# COSEQ_shield.net
KiCad netlist of a schematic drawn in EAGLE
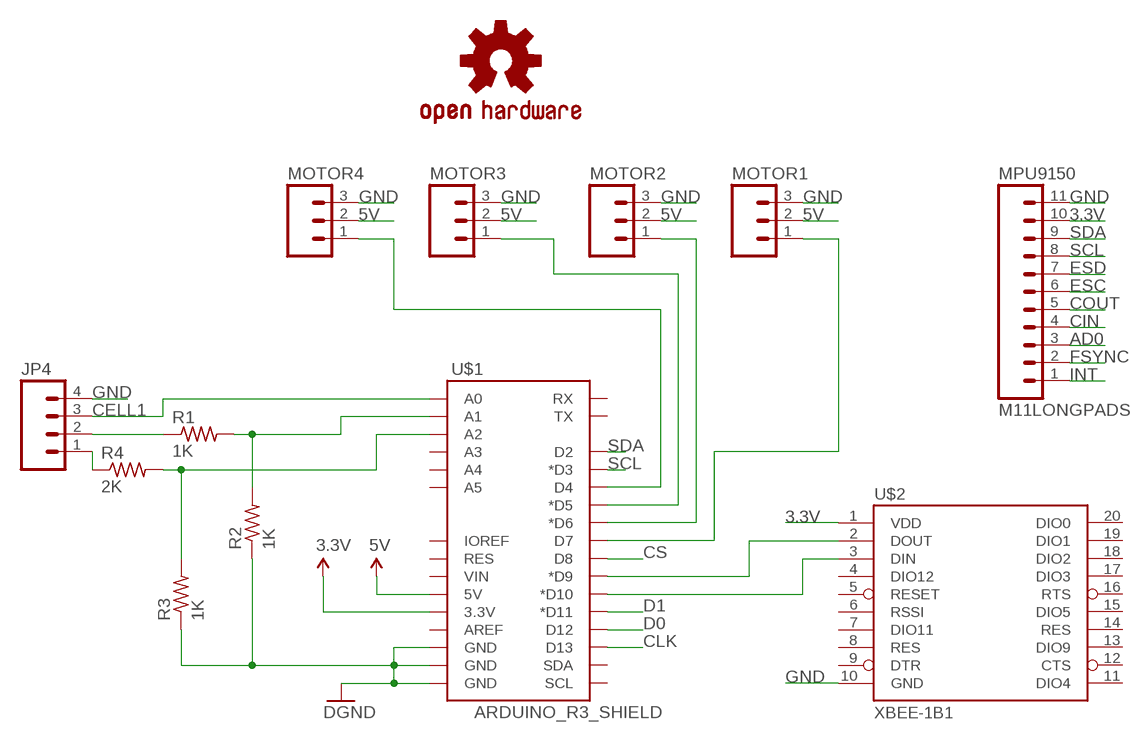
[diagram p0: schematic, sheet 1]

(export (version "E")
  (design (tool "Eeschema 10.0.6"))
  (components
    (comp (ref "JP4")
      (value "M04LONGPADS")
      (footprint "eagle-import:1X04_LONGPADS")
      (libsource (lib "eagle-import") (part "M04LONGPADS"))
    )
    (comp (ref "LOGO1")
      (value "OSHW-LOGOL")
      (footprint "eagle-import:OSHW-LOGO-L")
      (libsource (lib "eagle-import") (part "OSHW-LOGOL"))
    )
    (comp (ref "MOTOR1")
      (value "M03LONGPADS")
      (footprint "eagle-import:1X03_LONGPADS")
      (libsource (lib "eagle-import") (part "M03LONGPADS"))
    )
    (comp (ref "MOTOR2")
      (value "M03LONGPADS")
      (footprint "eagle-import:1X03_LONGPADS")
      (libsource (lib "eagle-import") (part "M03LONGPADS"))
    )
    (comp (ref "MOTOR3")
      (value "M03LONGPADS")
      (footprint "eagle-import:1X03_LONGPADS")
      (libsource (lib "eagle-import") (part "M03LONGPADS"))
    )
    (comp (ref "MOTOR4")
      (value "M03LONGPADS")
      (footprint "eagle-import:1X03_LONGPADS")
      (libsource (lib "eagle-import") (part "M03LONGPADS"))
    )
    (comp (ref "MPU9150")
      (value "M11LONGPADS")
      (footprint "eagle-import:1X11_LONGPADS")
      (libsource (lib "eagle-import") (part "M11LONGPADS"))
    )
    (comp (ref "R1")
      (value "1K")
      (footprint "eagle-import:RESISTOR")
      (libsource (lib "eagle-import") (part "RESISTOR1/6WATT"))
    )
    (comp (ref "R2")
      (value "1K")
      (footprint "eagle-import:RESISTOR")
      (libsource (lib "eagle-import") (part "RESISTOR1/6WATT"))
    )
    (comp (ref "R3")
      (value "1K")
      (footprint "eagle-import:RESISTOR")
      (libsource (lib "eagle-import") (part "RESISTOR1/6WATT"))
    )
    (comp (ref "R4")
      (value "2K")
      (footprint "eagle-import:RESISTOR")
      (libsource (lib "eagle-import") (part "RESISTOR1/6WATT"))
    )
    (comp (ref "U$1")
      (value "ARDUINO_R3_SHIELD")
      (footprint "eagle-import:UNO_R3_SHIELD")
      (libsource (lib "eagle-import") (part "ARDUINO_R3_SHIELD"))
    )
    (comp (ref "U$2")
      (value "XBEE-1B1")
      (footprint "eagle-import:XBEE-1")
      (libsource (lib "eagle-import") (part "XBEE-1B1"))
    )
  )
  (nets
    (net (code "1") (name "/AD0") (class "Default")
      (node (ref "MPU9150") (pin "3") (pinfunction "3_3") (pintype "passive"))
    )
    (net (code "2") (name "/CELL1") (class "Default")
      (node (ref "JP4") (pin "3") (pinfunction "3_3") (pintype "passive"))
      (node (ref "U$1") (pin "A0") (pinfunction "A0_A0") (pintype "bidirectional"))
    )
    (net (code "3") (name "/CIN") (class "Default")
      (node (ref "MPU9150") (pin "4") (pinfunction "4_4") (pintype "passive"))
    )
    (net (code "4") (name "/CLK") (class "Default")
      (node (ref "U$1") (pin "D13") (pinfunction "D13_D13") (pintype "bidirectional"))
    )
    (net (code "5") (name "/COUT") (class "Default")
      (node (ref "MPU9150") (pin "5") (pinfunction "5_5") (pintype "passive"))
    )
    (net (code "6") (name "/CS") (class "Default")
      (node (ref "U$1") (pin "D8") (pinfunction "D8_D8") (pintype "bidirectional"))
    )
    (net (code "7") (name "/D0") (class "Default")
      (node (ref "U$1") (pin "D12") (pinfunction "D12_D12") (pintype "bidirectional"))
    )
    (net (code "8") (name "/D1") (class "Default")
      (node (ref "U$1") (pin "D11") (pinfunction "*D11_D11") (pintype "bidirectional"))
    )
    (net (code "9") (name "/ESC") (class "Default")
      (node (ref "MPU9150") (pin "6") (pinfunction "6_6") (pintype "passive"))
    )
    (net (code "10") (name "/ESD") (class "Default")
      (node (ref "MPU9150") (pin "7") (pinfunction "7_7") (pintype "passive"))
    )
    (net (code "11") (name "/FSYNC") (class "Default")
      (node (ref "MPU9150") (pin "2") (pinfunction "2_2") (pintype "passive"))
    )
    (net (code "12") (name "/INT") (class "Default")
      (node (ref "MPU9150") (pin "1") (pinfunction "1_1") (pintype "passive"))
    )
    (net (code "13") (name "/SCL") (class "Default")
      (node (ref "MPU9150") (pin "8") (pinfunction "8_8") (pintype "passive"))
      (node (ref "U$1") (pin "D3") (pinfunction "*D3_D3") (pintype "bidirectional"))
    )
    (net (code "14") (name "/SDA") (class "Default")
      (node (ref "MPU9150") (pin "9") (pinfunction "9_9") (pintype "passive"))
      (node (ref "U$1") (pin "D2") (pinfunction "D2_D2") (pintype "bidirectional"))
    )
    (net (code "15") (name "3.3V") (class "Default")
      (node (ref "MPU9150") (pin "10") (pinfunction "10_10") (pintype "passive"))
      (node (ref "U$1") (pin "3.3V") (pinfunction "3.3V_3.3V") (pintype "bidirectional"))
      (node (ref "U$2") (pin "1") (pinfunction "VDD_1") (pintype "power_in"))
    )
    (net (code "16") (name "5V") (class "Default")
      (node (ref "MOTOR1") (pin "2") (pinfunction "2_2") (pintype "passive"))
      (node (ref "MOTOR2") (pin "2") (pinfunction "2_2") (pintype "passive"))
      (node (ref "MOTOR3") (pin "2") (pinfunction "2_2") (pintype "passive"))
      (node (ref "MOTOR4") (pin "2") (pinfunction "2_2") (pintype "passive"))
      (node (ref "U$1") (pin "5V") (pinfunction "5V_5V") (pintype "bidirectional"))
    )
    (net (code "17") (name "DGND") (class "Default")
      (node (ref "JP4") (pin "4") (pinfunction "4_4") (pintype "passive"))
      (node (ref "MOTOR1") (pin "3") (pinfunction "3_3") (pintype "passive"))
      (node (ref "MOTOR2") (pin "3") (pinfunction "3_3") (pintype "passive"))
      (node (ref "MOTOR3") (pin "3") (pinfunction "3_3") (pintype "passive"))
      (node (ref "MOTOR4") (pin "3") (pinfunction "3_3") (pintype "passive"))
      (node (ref "MPU9150") (pin "11") (pinfunction "11_11") (pintype "passive"))
      (node (ref "R2") (pin "1") (pinfunction "1_1") (pintype "passive"))
      (node (ref "R3") (pin "1") (pinfunction "1_1") (pintype "passive"))
      (node (ref "U$1") (pin "GND@0") (pinfunction "GND_GND@0") (pintype "bidirectional"))
      (node (ref "U$1") (pin "GND@1") (pinfunction "GND_GND@1") (pintype "bidirectional"))
      (node (ref "U$1") (pin "GND@2") (pinfunction "GND_GND@2") (pintype "bidirectional"))
      (node (ref "U$2") (pin "10") (pinfunction "GND_10") (pintype "power_in"))
    )
    (net (code "18") (name "Net-(JP4-Pad1)") (class "Default")
      (node (ref "JP4") (pin "1") (pinfunction "1_1") (pintype "passive"))
      (node (ref "R4") (pin "1") (pinfunction "1_1") (pintype "passive"))
    )
    (net (code "19") (name "Net-(JP4-Pad2)") (class "Default")
      (node (ref "JP4") (pin "2") (pinfunction "2_2") (pintype "passive"))
      (node (ref "R1") (pin "1") (pinfunction "1_1") (pintype "passive"))
    )
    (net (code "20") (name "Net-(MOTOR1-Pad1)") (class "Default")
      (node (ref "MOTOR1") (pin "1") (pinfunction "1_1") (pintype "passive"))
      (node (ref "U$1") (pin "D7") (pinfunction "D7_D7") (pintype "bidirectional"))
    )
    (net (code "21") (name "Net-(MOTOR4-Pad1)") (class "Default")
      (node (ref "MOTOR4") (pin "1") (pinfunction "1_1") (pintype "passive"))
      (node (ref "U$1") (pin "D4") (pinfunction "D4_D4") (pintype "bidirectional"))
    )
    (net (code "22") (name "Net-(R1-Pad2)") (class "Default")
      (node (ref "R1") (pin "2") (pinfunction "2_2") (pintype "passive"))
      (node (ref "R2") (pin "2") (pinfunction "2_2") (pintype "passive"))
      (node (ref "U$1") (pin "A1") (pinfunction "A1_A1") (pintype "bidirectional"))
    )
    (net (code "23") (name "Net-(R3-Pad2)") (class "Default")
      (node (ref "R3") (pin "2") (pinfunction "2_2") (pintype "passive"))
      (node (ref "R4") (pin "2") (pinfunction "2_2") (pintype "passive"))
      (node (ref "U$1") (pin "A2") (pinfunction "A2_A2") (pintype "bidirectional"))
    )
    (net (code "24") (name "Net-(U$1-*D5)") (class "Default")
      (node (ref "MOTOR3") (pin "1") (pinfunction "1_1") (pintype "passive"))
      (node (ref "U$1") (pin "D5") (pinfunction "*D5_D5") (pintype "bidirectional"))
    )
    (net (code "25") (name "Net-(U$1-*D6)") (class "Default")
      (node (ref "MOTOR2") (pin "1") (pinfunction "1_1") (pintype "passive"))
      (node (ref "U$1") (pin "D6") (pinfunction "*D6_D6") (pintype "bidirectional"))
    )
    (net (code "26") (name "Net-(U$1-*D9)") (class "Default")
      (node (ref "U$1") (pin "D9") (pinfunction "*D9_D9") (pintype "bidirectional"))
      (node (ref "U$2") (pin "2") (pinfunction "DOUT_2") (pintype "output"))
    )
    (net (code "27") (name "Net-(U$1-*D10)") (class "Default")
      (node (ref "U$1") (pin "D10") (pinfunction "*D10_D10") (pintype "bidirectional"))
      (node (ref "U$2") (pin "3") (pinfunction "DIN_3") (pintype "input"))
    )
    (net (code "28") (name "unconnected-(U$1-PadA3)") (class "Default")
      (node (ref "U$1") (pin "A3") (pinfunction "A3_A3") (pintype "bidirectional"))
    )
    (net (code "29") (name "unconnected-(U$1-PadA4)") (class "Default")
      (node (ref "U$1") (pin "A4") (pinfunction "A4_A4") (pintype "bidirectional"))
    )
    (net (code "30") (name "unconnected-(U$1-PadA5)") (class "Default")
      (node (ref "U$1") (pin "A5") (pinfunction "A5_A5") (pintype "bidirectional"))
    )
    (net (code "31") (name "unconnected-(U$1-PadAREF)") (class "Default")
      (node (ref "U$1") (pin "AREF") (pinfunction "AREF_AREF") (pintype "bidirectional"))
    )
    (net (code "32") (name "unconnected-(U$1-PadIOREF)") (class "Default")
      (node (ref "U$1") (pin "IOREF") (pinfunction "IOREF_IOREF") (pintype "bidirectional"))
    )
    (net (code "33") (name "unconnected-(U$1-PadRES)") (class "Default")
      (node (ref "U$1") (pin "RES") (pinfunction "RES_RES") (pintype "bidirectional"))
    )
    (net (code "34") (name "unconnected-(U$1-PadRX)") (class "Default")
      (node (ref "U$1") (pin "RX") (pinfunction "RX_RX") (pintype "bidirectional"))
    )
    (net (code "35") (name "unconnected-(U$1-PadSCL)") (class "Default")
      (node (ref "U$1") (pin "SCL") (pinfunction "SCL_SCL") (pintype "bidirectional"))
    )
    (net (code "36") (name "unconnected-(U$1-PadSDA)") (class "Default")
      (node (ref "U$1") (pin "SDA") (pinfunction "SDA_SDA") (pintype "bidirectional"))
    )
    (net (code "37") (name "unconnected-(U$1-PadTX)") (class "Default")
      (node (ref "U$1") (pin "TX") (pinfunction "TX_TX") (pintype "bidirectional"))
    )
    (net (code "38") (name "unconnected-(U$1-PadVIN)") (class "Default")
      (node (ref "U$1") (pin "VIN") (pinfunction "VIN_VIN") (pintype "bidirectional"))
    )
    (net (code "39") (name "unconnected-(U$2-CTS-Pad12)") (class "Default")
      (node (ref "U$2") (pin "12") (pinfunction "CTS_12") (pintype "output"))
    )
    (net (code "40") (name "unconnected-(U$2-DIO0-Pad20)") (class "Default")
      (node (ref "U$2") (pin "20") (pinfunction "DIO0_20") (pintype "bidirectional"))
    )
    (net (code "41") (name "unconnected-(U$2-DIO1-Pad19)") (class "Default")
      (node (ref "U$2") (pin "19") (pinfunction "DIO1_19") (pintype "bidirectional"))
    )
    (net (code "42") (name "unconnected-(U$2-DIO2-Pad18)") (class "Default")
      (node (ref "U$2") (pin "18") (pinfunction "DIO2_18") (pintype "bidirectional"))
    )
    (net (code "43") (name "unconnected-(U$2-DIO3-Pad17)") (class "Default")
      (node (ref "U$2") (pin "17") (pinfunction "DIO3_17") (pintype "bidirectional"))
    )
    (net (code "44") (name "unconnected-(U$2-DIO4-Pad11)") (class "Default")
      (node (ref "U$2") (pin "11") (pinfunction "DIO4_11") (pintype "bidirectional"))
    )
    (net (code "45") (name "unconnected-(U$2-DIO5-Pad15)") (class "Default")
      (node (ref "U$2") (pin "15") (pinfunction "DIO5_15") (pintype "bidirectional"))
    )
    (net (code "46") (name "unconnected-(U$2-DIO9-Pad13)") (class "Default")
      (node (ref "U$2") (pin "13") (pinfunction "DIO9_13") (pintype "bidirectional"))
    )
    (net (code "47") (name "unconnected-(U$2-DIO11-Pad7)") (class "Default")
      (node (ref "U$2") (pin "7") (pinfunction "DIO11_7") (pintype "bidirectional"))
    )
    (net (code "48") (name "unconnected-(U$2-DIO12-Pad4)") (class "Default")
      (node (ref "U$2") (pin "4") (pinfunction "DIO12_4") (pintype "bidirectional"))
    )
    (net (code "49") (name "unconnected-(U$2-DTR-Pad9)") (class "Default")
      (node (ref "U$2") (pin "9") (pinfunction "DTR_9") (pintype "bidirectional"))
    )
    (net (code "50") (name "unconnected-(U$2-RES-Pad8)") (class "Default")
      (node (ref "U$2") (pin "8") (pinfunction "RES_8") (pintype "bidirectional"))
    )
    (net (code "51") (name "unconnected-(U$2-RES-Pad14)") (class "Default")
      (node (ref "U$2") (pin "14") (pinfunction "RES_14") (pintype "bidirectional"))
    )
    (net (code "52") (name "unconnected-(U$2-RESET-Pad5)") (class "Default")
      (node (ref "U$2") (pin "5") (pinfunction "RESET_5") (pintype "input"))
    )
    (net (code "53") (name "unconnected-(U$2-RSSI-Pad6)") (class "Default")
      (node (ref "U$2") (pin "6") (pinfunction "RSSI_6") (pintype "bidirectional"))
    )
    (net (code "54") (name "unconnected-(U$2-RTS-Pad16)") (class "Default")
      (node (ref "U$2") (pin "16") (pinfunction "RTS_16") (pintype "input"))
    )
  )
)
